# 0120-DACz4.net
KiCad netlist of a schematic drawn in EAGLE
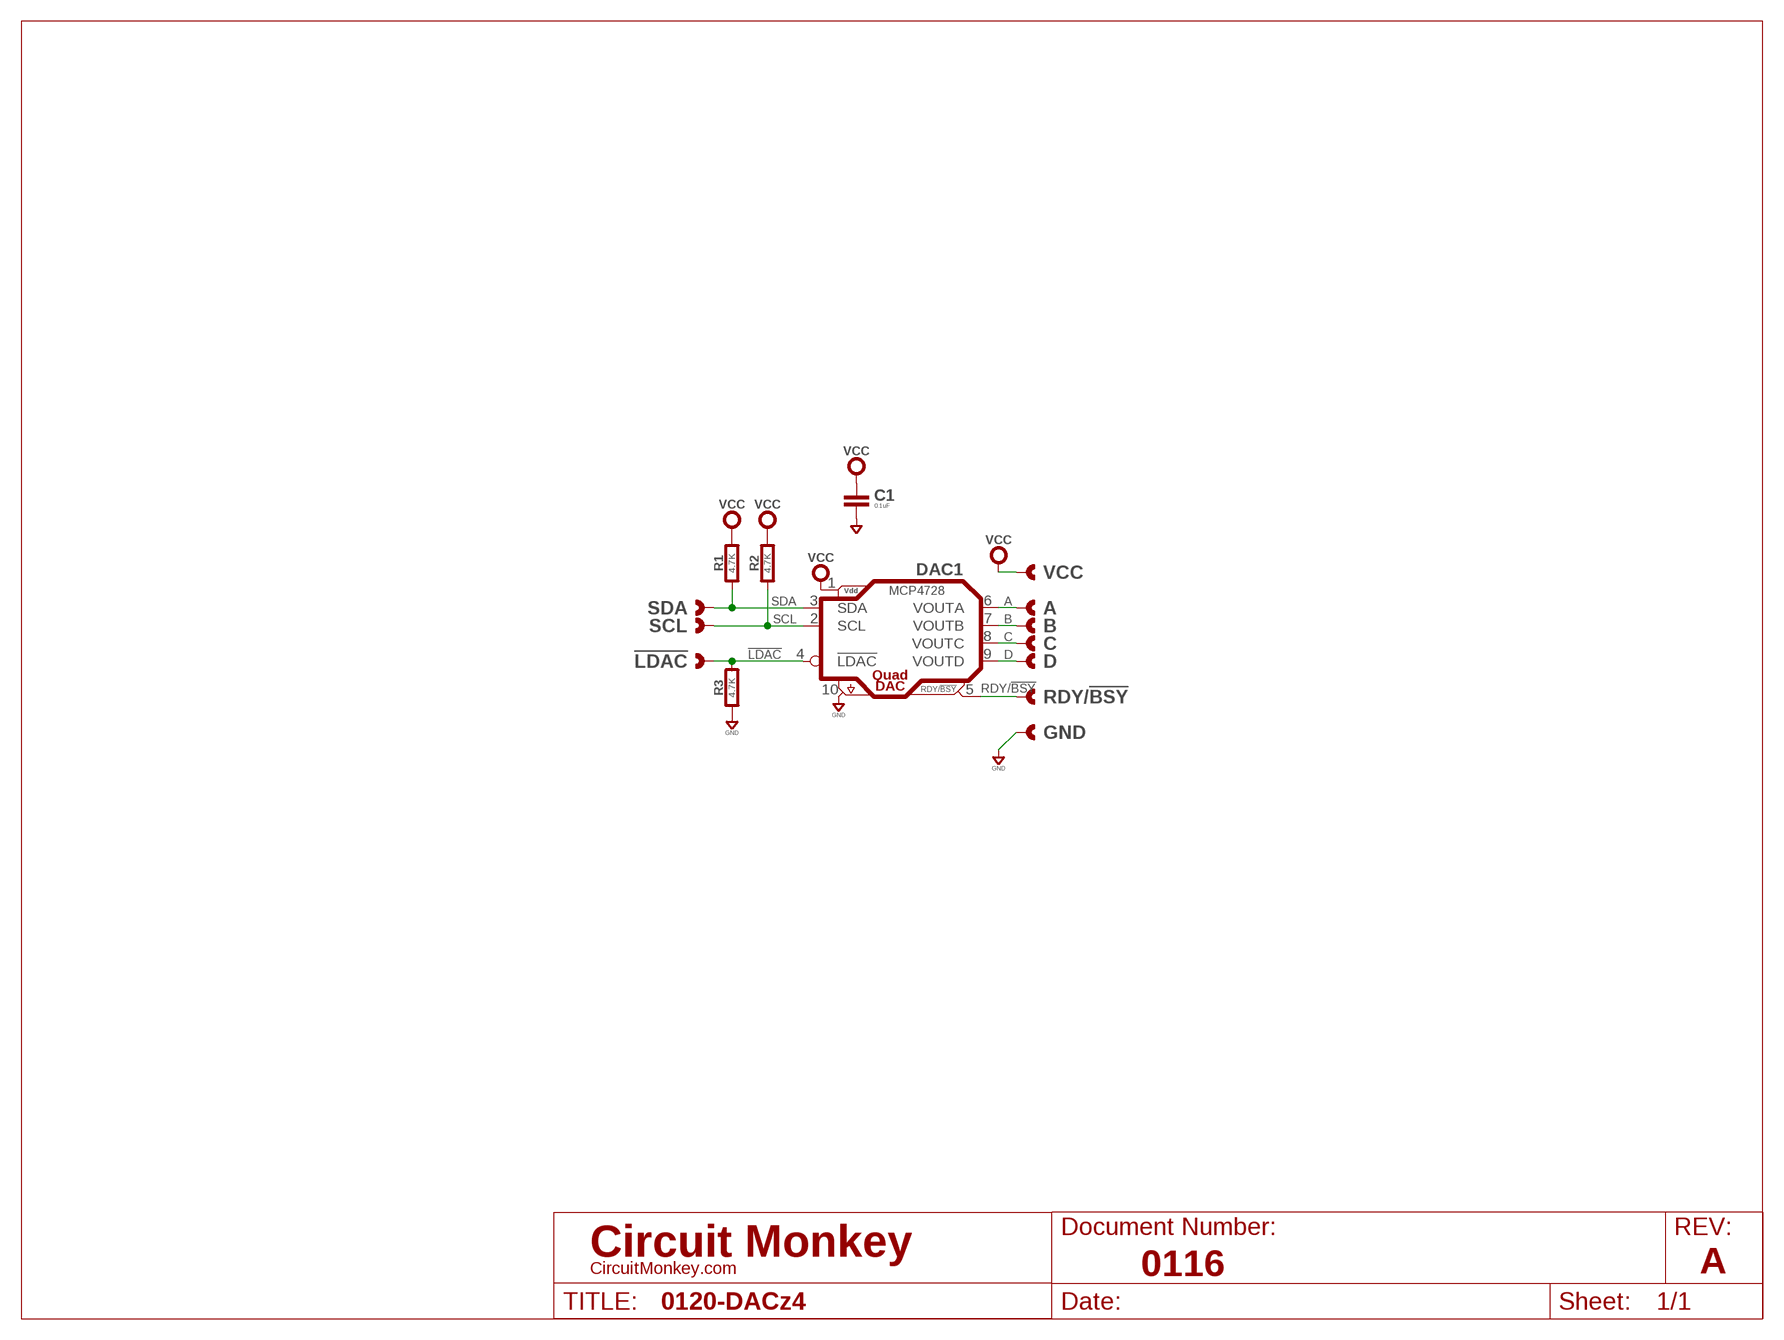
[diagram p0: schematic, sheet 1]

(export (version "E")
  (design (tool "Eeschema 10.0.6"))
  (components
    (comp (ref "!LDAC")
      (value "CAST-01X12.00MM")
      (footprint "eagle-import:CAST01-2.00MM")
      (libsource (lib "eagle-import") (part "CAST-01X12.00MM"))
    )
    (comp (ref "A")
      (value "CAST-01X12.00MM")
      (footprint "eagle-import:CAST01-2.00MM")
      (libsource (lib "eagle-import") (part "CAST-01X12.00MM"))
    )
    (comp (ref "B")
      (value "CAST-01X12.00MM")
      (footprint "eagle-import:CAST01-2.00MM")
      (libsource (lib "eagle-import") (part "CAST-01X12.00MM"))
    )
    (comp (ref "C")
      (value "CAST-01X12.00MM")
      (footprint "eagle-import:CAST01-2.00MM")
      (libsource (lib "eagle-import") (part "CAST-01X12.00MM"))
    )
    (comp (ref "C1")
      (value "0.1uF")
      (footprint "eagle-import:0603-CAP")
      (libsource (lib "eagle-import") (part "CAPACITOR0603"))
    )
    (comp (ref "D")
      (value "CAST-01X12.00MM")
      (footprint "eagle-import:CAST01-2.00MM")
      (libsource (lib "eagle-import") (part "CAST-01X12.00MM"))
    )
    (comp (ref "DAC1")
      (value "MCP4728")
      (footprint "eagle-import:MSOP10")
      (fields (field (name "MFR") "Microchip"))
      (libsource (lib "eagle-import") (part "MCP4728"))
    )
    (comp (ref "GND")
      (value "CAST-01X12.00MM")
      (footprint "eagle-import:CAST01-2.00MM")
      (libsource (lib "eagle-import") (part "CAST-01X12.00MM"))
    )
    (comp (ref "R1")
      (value "4.7K")
      (footprint "eagle-import:0603-RES")
      (libsource (lib "eagle-import") (part "RESISTOR0603"))
    )
    (comp (ref "R2")
      (value "4.7K")
      (footprint "eagle-import:0603-RES")
      (libsource (lib "eagle-import") (part "RESISTOR0603"))
    )
    (comp (ref "R3")
      (value "4.7K")
      (footprint "eagle-import:0603-RES")
      (libsource (lib "eagle-import") (part "RESISTOR0603"))
    )
    (comp (ref "RDY/!BSY")
      (value "CAST-01X12.00MM")
      (footprint "eagle-import:CAST01-2.00MM")
      (libsource (lib "eagle-import") (part "CAST-01X12.00MM"))
    )
    (comp (ref "SCL")
      (value "CAST-01X12.00MM")
      (footprint "eagle-import:CAST01-2.00MM")
      (libsource (lib "eagle-import") (part "CAST-01X12.00MM"))
    )
    (comp (ref "SDA")
      (value "CAST-01X12.00MM")
      (footprint "eagle-import:CAST01-2.00MM")
      (libsource (lib "eagle-import") (part "CAST-01X12.00MM"))
    )
    (comp (ref "VCC")
      (value "CAST-01X12.00MM")
      (footprint "eagle-import:CAST01-2.00MM")
      (libsource (lib "eagle-import") (part "CAST-01X12.00MM"))
    )
  )
  (nets
    (net (code "1") (name "/A") (class "Default")
      (node (ref "A") (pin "1") (pinfunction "1_1") (pintype "bidirectional"))
      (node (ref "A") (pin "P$1") (pinfunction "1_P$1") (pintype "bidirectional"))
      (node (ref "A") (pin "P$2") (pinfunction "1_P$2") (pintype "bidirectional"))
      (node (ref "DAC1") (pin "6") (pinfunction "VOUTA_6") (pintype "bidirectional"))
    )
    (net (code "2") (name "/B") (class "Default")
      (node (ref "B") (pin "1") (pinfunction "1_1") (pintype "bidirectional"))
      (node (ref "B") (pin "P$1") (pinfunction "1_P$1") (pintype "bidirectional"))
      (node (ref "B") (pin "P$2") (pinfunction "1_P$2") (pintype "bidirectional"))
      (node (ref "DAC1") (pin "7") (pinfunction "VOUTB_7") (pintype "bidirectional"))
    )
    (net (code "3") (name "/C") (class "Default")
      (node (ref "C") (pin "1") (pinfunction "1_1") (pintype "bidirectional"))
      (node (ref "C") (pin "P$1") (pinfunction "1_P$1") (pintype "bidirectional"))
      (node (ref "C") (pin "P$2") (pinfunction "1_P$2") (pintype "bidirectional"))
      (node (ref "DAC1") (pin "8") (pinfunction "VOUTC_8") (pintype "bidirectional"))
    )
    (net (code "4") (name "/D") (class "Default")
      (node (ref "D") (pin "1") (pinfunction "1_1") (pintype "bidirectional"))
      (node (ref "D") (pin "P$1") (pinfunction "1_P$1") (pintype "bidirectional"))
      (node (ref "D") (pin "P$2") (pinfunction "1_P$2") (pintype "bidirectional"))
      (node (ref "DAC1") (pin "9") (pinfunction "VOUTD_9") (pintype "bidirectional"))
    )
    (net (code "5") (name "/RDY{slash}~{BSY}") (class "Default")
      (node (ref "DAC1") (pin "5") (pinfunction "RDY/~{BSY}_5") (pintype "bidirectional"))
      (node (ref "RDY/!BSY") (pin "1") (pinfunction "1_1") (pintype "bidirectional"))
      (node (ref "RDY/!BSY") (pin "P$1") (pinfunction "1_P$1") (pintype "bidirectional"))
      (node (ref "RDY/!BSY") (pin "P$2") (pinfunction "1_P$2") (pintype "bidirectional"))
    )
    (net (code "6") (name "/SCL") (class "Default")
      (node (ref "DAC1") (pin "2") (pinfunction "SCL_2") (pintype "bidirectional"))
      (node (ref "R2") (pin "1") (pinfunction "1_1") (pintype "passive"))
      (node (ref "SCL") (pin "1") (pinfunction "1_1") (pintype "bidirectional"))
      (node (ref "SCL") (pin "P$1") (pinfunction "1_P$1") (pintype "bidirectional"))
      (node (ref "SCL") (pin "P$2") (pinfunction "1_P$2") (pintype "bidirectional"))
    )
    (net (code "7") (name "/SDA") (class "Default")
      (node (ref "DAC1") (pin "3") (pinfunction "SDA_3") (pintype "bidirectional"))
      (node (ref "R1") (pin "1") (pinfunction "1_1") (pintype "passive"))
      (node (ref "SDA") (pin "1") (pinfunction "1_1") (pintype "bidirectional"))
      (node (ref "SDA") (pin "P$1") (pinfunction "1_P$1") (pintype "bidirectional"))
      (node (ref "SDA") (pin "P$2") (pinfunction "1_P$2") (pintype "bidirectional"))
    )
    (net (code "8") (name "/~{LDAC}") (class "Default")
      (node (ref "!LDAC") (pin "1") (pinfunction "1_1") (pintype "bidirectional"))
      (node (ref "!LDAC") (pin "P$1") (pinfunction "1_P$1") (pintype "bidirectional"))
      (node (ref "!LDAC") (pin "P$2") (pinfunction "1_P$2") (pintype "bidirectional"))
      (node (ref "DAC1") (pin "4") (pinfunction "~{LDAC}_4") (pintype "bidirectional"))
      (node (ref "R3") (pin "2") (pinfunction "2_2") (pintype "passive"))
    )
    (net (code "9") (name "GND") (class "Default")
      (node (ref "C1") (pin "2") (pinfunction "2_2") (pintype "passive"))
      (node (ref "DAC1") (pin "10") (pinfunction "GND_10") (pintype "power_in"))
      (node (ref "GND") (pin "1") (pinfunction "1_1") (pintype "bidirectional"))
      (node (ref "GND") (pin "P$1") (pinfunction "1_P$1") (pintype "bidirectional"))
      (node (ref "GND") (pin "P$2") (pinfunction "1_P$2") (pintype "bidirectional"))
      (node (ref "R3") (pin "1") (pinfunction "1_1") (pintype "passive"))
    )
    (net (code "10") (name "VCC") (class "Default")
      (node (ref "C1") (pin "1") (pinfunction "1_1") (pintype "passive"))
      (node (ref "DAC1") (pin "1") (pinfunction "VDD_1") (pintype "power_in"))
      (node (ref "R1") (pin "2") (pinfunction "2_2") (pintype "passive"))
      (node (ref "R2") (pin "2") (pinfunction "2_2") (pintype "passive"))
      (node (ref "VCC") (pin "1") (pinfunction "1_1") (pintype "bidirectional"))
      (node (ref "VCC") (pin "P$1") (pinfunction "1_P$1") (pintype "bidirectional"))
      (node (ref "VCC") (pin "P$2") (pinfunction "1_P$2") (pintype "bidirectional"))
    )
  )
)
